# Un_TTL.net
KiCad netlist of a schematic drawn in EAGLE
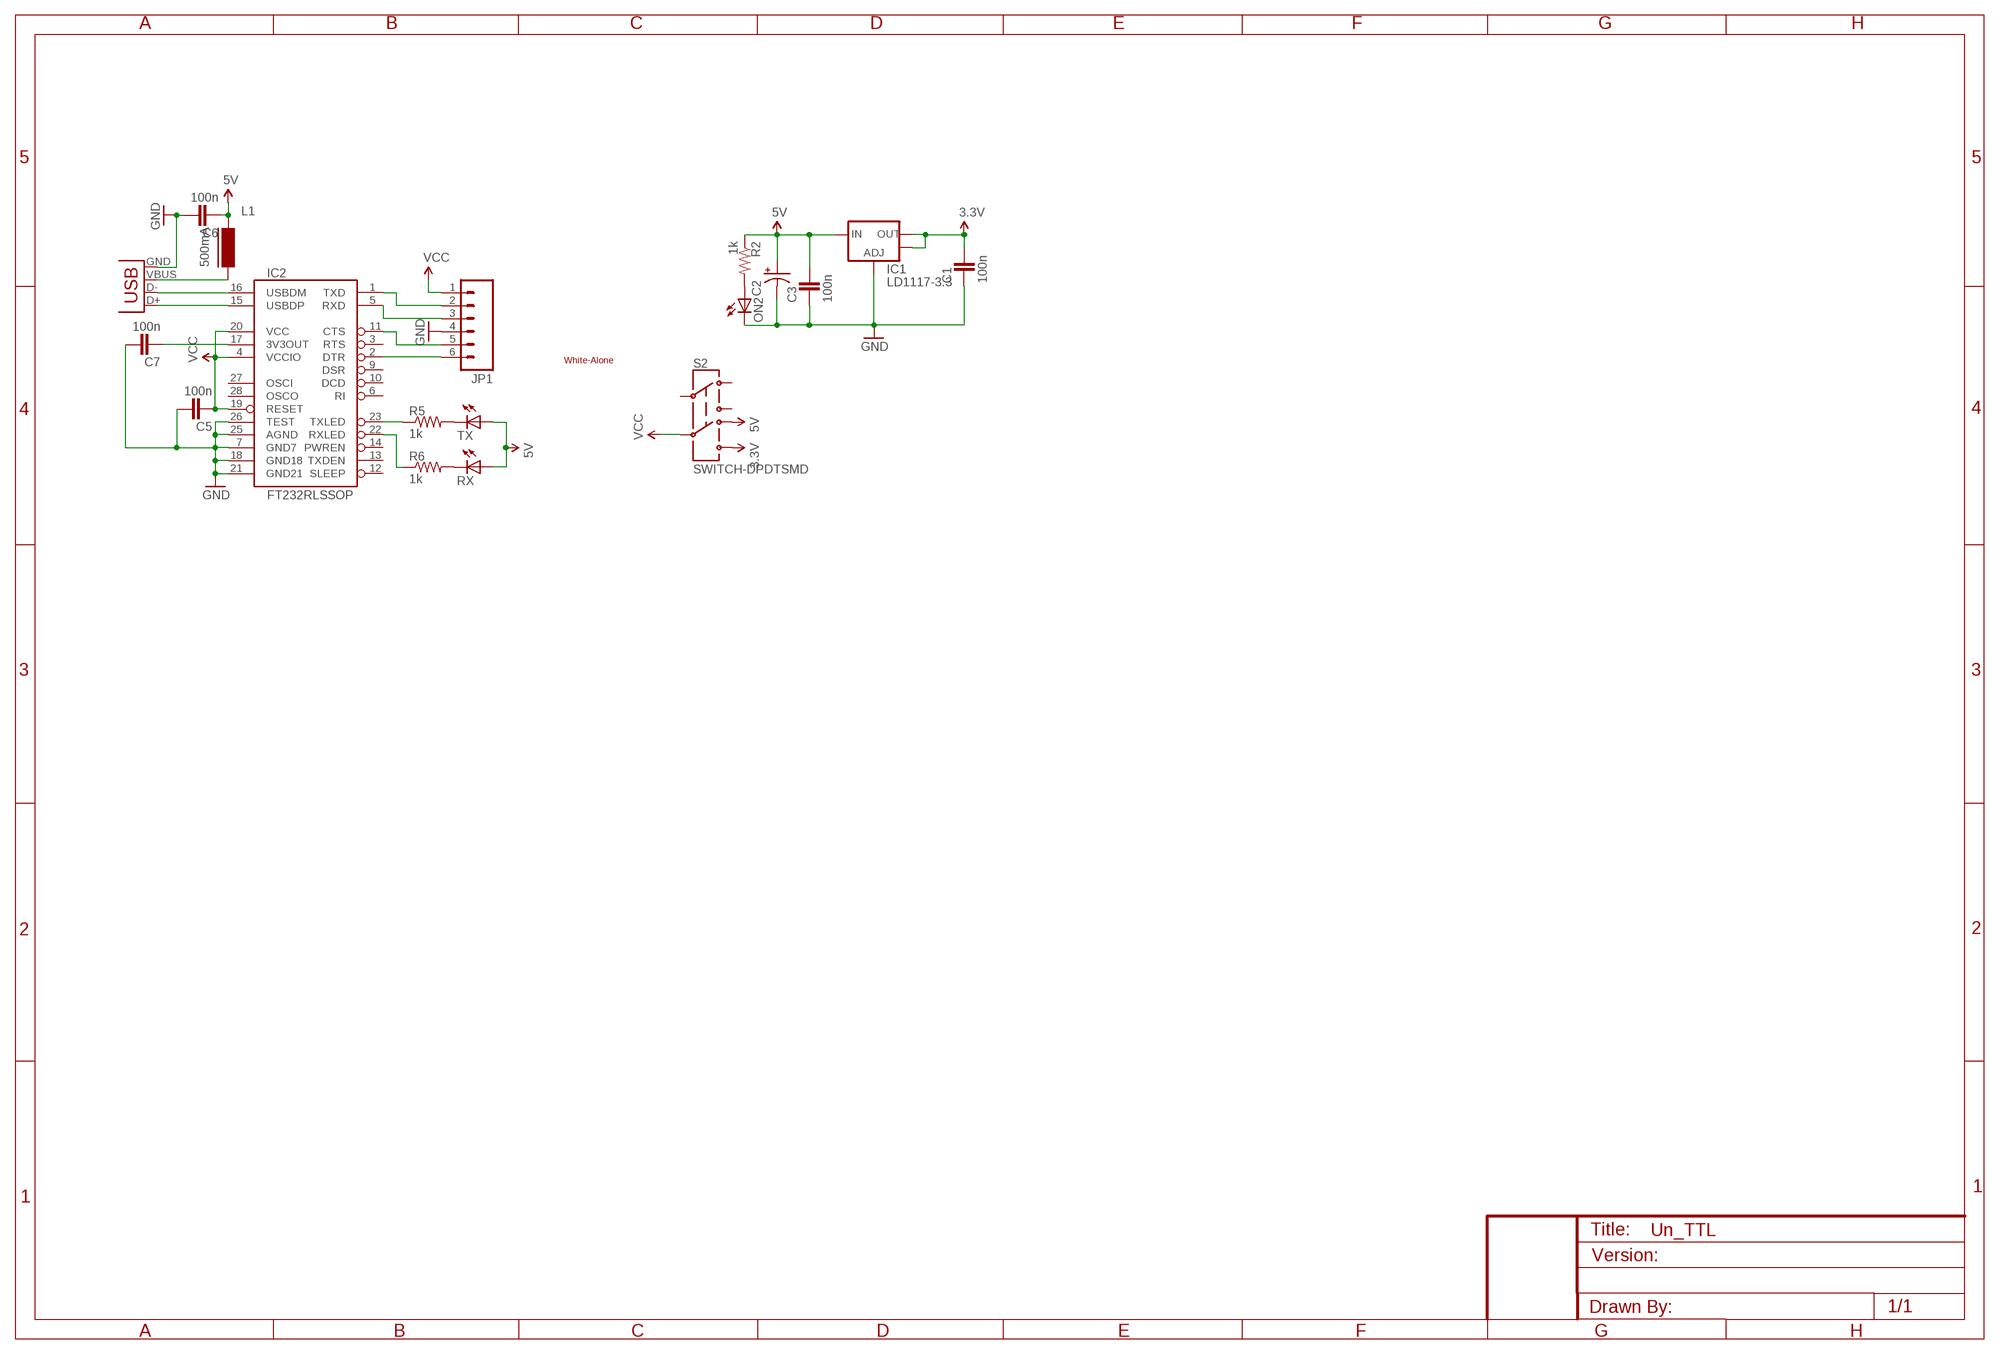
[diagram p0: schematic, sheet 1]

(export (version "E")
  (design (tool "Eeschema 10.0.6"))
  (components
    (comp (ref "C1")
      (value "100n")
      (footprint "eagle-import:0603-CAP")
      (libsource (lib "eagle-import") (part "CAP0603"))
    )
    (comp (ref "C2")
      (value "CAP_POL1206")
      (footprint "eagle-import:EIA3216")
      (libsource (lib "eagle-import") (part "CAP_POL1206"))
    )
    (comp (ref "C3")
      (value "100n")
      (footprint "eagle-import:0603-CAP")
      (libsource (lib "eagle-import") (part "CAP0603"))
    )
    (comp (ref "C5")
      (value "100n")
      (footprint "eagle-import:0603-CAP")
      (libsource (lib "eagle-import") (part "CAP0603"))
    )
    (comp (ref "C6")
      (value "100n")
      (footprint "eagle-import:0603-CAP")
      (libsource (lib "eagle-import") (part "CAP0603"))
    )
    (comp (ref "C7")
      (value "100n")
      (footprint "eagle-import:0603-CAP")
      (libsource (lib "eagle-import") (part "CAP0603"))
    )
    (comp (ref "IC1")
      (value "LD1117-3.3")
      (footprint "eagle-import:SOT223")
      (libsource (lib "eagle-import") (part "V_REG_LM1117SOT223"))
    )
    (comp (ref "IC2")
      (value "FT232RLSSOP")
      (footprint "eagle-import:SSOP28DB")
      (libsource (lib "eagle-import") (part "FT232RLSSOP"))
    )
    (comp (ref "JP1")
      (value "M06SIP")
      (footprint "eagle-import:1X06")
      (libsource (lib "eagle-import") (part "M06SIP"))
    )
    (comp (ref "L1")
      (value "500mA")
      (footprint "eagle-import:FB805")
      (libsource (lib "eagle-import") (part "FERRITE-0805"))
    )
    (comp (ref "ON2")
      (value "LED0805")
      (footprint "eagle-import:LED-0805")
      (libsource (lib "eagle-import") (part "LED0805"))
    )
    (comp (ref "R2")
      (value "1k")
      (footprint "eagle-import:0603-RES")
      (libsource (lib "eagle-import") (part "RESISTOR0603-RES"))
    )
    (comp (ref "R5")
      (value "1k")
      (footprint "eagle-import:0603-RES")
      (libsource (lib "eagle-import") (part "RESISTOR0603-RES"))
    )
    (comp (ref "R6")
      (value "1k")
      (footprint "eagle-import:0603-RES")
      (libsource (lib "eagle-import") (part "RESISTOR0603-RES"))
    )
    (comp (ref "RX")
      (value "LED0805")
      (footprint "eagle-import:LED-0805")
      (libsource (lib "eagle-import") (part "LED0805"))
    )
    (comp (ref "S2")
      (value "SWITCH-DPDTSMD")
      (footprint "eagle-import:AYZ0202")
      (libsource (lib "eagle-import") (part "SWITCH-DPDTSMD"))
    )
    (comp (ref "TX")
      (value "LED0805")
      (footprint "eagle-import:LED-0805")
      (libsource (lib "eagle-import") (part "LED0805"))
    )
    (comp (ref "U$2")
      (value "WHITE-ALONE_0")
      (footprint "eagle-import:WHITE-ALONE_0")
      (libsource (lib "eagle-import") (part "WHITE-ALONE_0"))
    )
    (comp (ref "X1")
      (value "USBSMD")
      (footprint "eagle-import:USB-MINIB")
      (libsource (lib "eagle-import") (part "USBSMD"))
    )
  )
  (nets
    (net (code "1") (name "3.3V") (class "Default")
      (node (ref "C1") (pin "1") (pinfunction "1_1") (pintype "passive"))
      (node (ref "IC1") (pin "2") (pinfunction "OUT_2") (pintype "output"))
      (node (ref "IC1") (pin "4") (pinfunction "OUT_4") (pintype "output"))
      (node (ref "S2") (pin "6") (pinfunction "6_6") (pintype "bidirectional"))
    )
    (net (code "2") (name "5V") (class "Default")
      (node (ref "C2") (pin "A") (pinfunction "+_A") (pintype "passive"))
      (node (ref "C3") (pin "1") (pinfunction "1_1") (pintype "passive"))
      (node (ref "C6") (pin "2") (pinfunction "2_2") (pintype "passive"))
      (node (ref "IC1") (pin "3") (pinfunction "IN_3") (pintype "input"))
      (node (ref "L1") (pin "1") (pinfunction "1_1") (pintype "passive"))
      (node (ref "R2") (pin "1") (pinfunction "1_1") (pintype "passive"))
      (node (ref "RX") (pin "1") (pinfunction "A_1") (pintype "passive"))
      (node (ref "S2") (pin "4") (pinfunction "4_4") (pintype "bidirectional"))
      (node (ref "TX") (pin "1") (pinfunction "A_1") (pintype "passive"))
    )
    (net (code "3") (name "GND") (class "Default")
      (node (ref "C1") (pin "2") (pinfunction "2_2") (pintype "passive"))
      (node (ref "C2") (pin "C") (pinfunction "-_C") (pintype "passive"))
      (node (ref "C3") (pin "2") (pinfunction "2_2") (pintype "passive"))
      (node (ref "C5") (pin "1") (pinfunction "1_1") (pintype "passive"))
      (node (ref "C6") (pin "1") (pinfunction "1_1") (pintype "passive"))
      (node (ref "C7") (pin "1") (pinfunction "1_1") (pintype "passive"))
      (node (ref "IC1") (pin "1") (pinfunction "ADJ_1") (pintype "input"))
      (node (ref "IC2") (pin "18") (pinfunction "GND18_18") (pintype "power_in"))
      (node (ref "IC2") (pin "21") (pinfunction "GND21_21") (pintype "power_in"))
      (node (ref "IC2") (pin "25") (pinfunction "AGND_25") (pintype "power_in"))
      (node (ref "IC2") (pin "26") (pinfunction "TEST_26") (pintype "input"))
      (node (ref "IC2") (pin "7") (pinfunction "GND7_7") (pintype "power_in"))
      (node (ref "JP1") (pin "4") (pinfunction "4_4") (pintype "passive"))
      (node (ref "ON2") (pin "2") (pinfunction "C_2") (pintype "passive"))
      (node (ref "X1") (pin "GND") (pinfunction "GND_GND") (pintype "bidirectional"))
    )
    (net (code "4") (name "Net-(IC2-3V3OUT)") (class "Default")
      (node (ref "C7") (pin "2") (pinfunction "2_2") (pintype "passive"))
      (node (ref "IC2") (pin "17") (pinfunction "3V3OUT_17") (pintype "output"))
    )
    (net (code "5") (name "Net-(IC2-CTS)") (class "Default")
      (node (ref "IC2") (pin "11") (pinfunction "CTS_11") (pintype "input"))
      (node (ref "JP1") (pin "5") (pinfunction "5_5") (pintype "passive"))
    )
    (net (code "6") (name "Net-(IC2-DTR)") (class "Default")
      (node (ref "IC2") (pin "2") (pinfunction "DTR_2") (pintype "output"))
      (node (ref "JP1") (pin "6") (pinfunction "6_6") (pintype "passive"))
    )
    (net (code "7") (name "Net-(IC2-RXD)") (class "Default")
      (node (ref "IC2") (pin "5") (pinfunction "RXD_5") (pintype "input"))
      (node (ref "JP1") (pin "3") (pinfunction "3_3") (pintype "passive"))
    )
    (net (code "8") (name "Net-(IC2-RXLED)") (class "Default")
      (node (ref "IC2") (pin "22") (pinfunction "RXLED_22") (pintype "input"))
      (node (ref "R6") (pin "1") (pinfunction "1_1") (pintype "passive"))
    )
    (net (code "9") (name "Net-(IC2-TXD)") (class "Default")
      (node (ref "IC2") (pin "1") (pinfunction "TXD_1") (pintype "output"))
      (node (ref "JP1") (pin "2") (pinfunction "2_2") (pintype "passive"))
    )
    (net (code "10") (name "Net-(IC2-TXLED)") (class "Default")
      (node (ref "IC2") (pin "23") (pinfunction "TXLED_23") (pintype "input"))
      (node (ref "R5") (pin "1") (pinfunction "1_1") (pintype "passive"))
    )
    (net (code "11") (name "Net-(IC2-USBDM)") (class "Default")
      (node (ref "IC2") (pin "16") (pinfunction "USBDM_16") (pintype "bidirectional"))
      (node (ref "X1") (pin "D-") (pinfunction "D-_D-") (pintype "bidirectional"))
    )
    (net (code "12") (name "Net-(IC2-USBDP)") (class "Default")
      (node (ref "IC2") (pin "15") (pinfunction "USBDP_15") (pintype "bidirectional"))
      (node (ref "X1") (pin "D+") (pinfunction "D+_D+") (pintype "bidirectional"))
    )
    (net (code "13") (name "Net-(L1-Pad2)") (class "Default")
      (node (ref "L1") (pin "2") (pinfunction "2_2") (pintype "passive"))
      (node (ref "X1") (pin "VBUS") (pinfunction "VBUS_VBUS") (pintype "bidirectional"))
    )
    (net (code "14") (name "Net-(ON2-A)") (class "Default")
      (node (ref "ON2") (pin "1") (pinfunction "A_1") (pintype "passive"))
      (node (ref "R2") (pin "2") (pinfunction "2_2") (pintype "passive"))
    )
    (net (code "15") (name "Net-(RX-C)") (class "Default")
      (node (ref "R6") (pin "2") (pinfunction "2_2") (pintype "passive"))
      (node (ref "RX") (pin "2") (pinfunction "C_2") (pintype "passive"))
    )
    (net (code "16") (name "Net-(TX-C)") (class "Default")
      (node (ref "R5") (pin "2") (pinfunction "2_2") (pintype "passive"))
      (node (ref "TX") (pin "2") (pinfunction "C_2") (pintype "passive"))
    )
    (net (code "17") (name "VCC") (class "Default")
      (node (ref "C5") (pin "2") (pinfunction "2_2") (pintype "passive"))
      (node (ref "IC2") (pin "19") (pinfunction "RESET_19") (pintype "input"))
      (node (ref "IC2") (pin "20") (pinfunction "VCC_20") (pintype "power_in"))
      (node (ref "IC2") (pin "4") (pinfunction "VCCIO_4") (pintype "power_in"))
      (node (ref "JP1") (pin "1") (pinfunction "1_1") (pintype "passive"))
      (node (ref "S2") (pin "5") (pinfunction "5_5") (pintype "bidirectional"))
    )
    (net (code "18") (name "unconnected-(IC2-DCD-Pad10)") (class "Default")
      (node (ref "IC2") (pin "10") (pinfunction "DCD_10") (pintype "input"))
    )
    (net (code "19") (name "unconnected-(IC2-DSR-Pad9)") (class "Default")
      (node (ref "IC2") (pin "9") (pinfunction "DSR_9") (pintype "input"))
    )
    (net (code "20") (name "unconnected-(IC2-OSCI-Pad27)") (class "Default")
      (node (ref "IC2") (pin "27") (pinfunction "OSCI_27") (pintype "input"))
    )
    (net (code "21") (name "unconnected-(IC2-OSCO-Pad28)") (class "Default")
      (node (ref "IC2") (pin "28") (pinfunction "OSCO_28") (pintype "output"))
    )
    (net (code "22") (name "unconnected-(IC2-PWREN-Pad14)") (class "Default")
      (node (ref "IC2") (pin "14") (pinfunction "PWREN_14") (pintype "input"))
    )
    (net (code "23") (name "unconnected-(IC2-RI-Pad6)") (class "Default")
      (node (ref "IC2") (pin "6") (pinfunction "RI_6") (pintype "input"))
    )
    (net (code "24") (name "unconnected-(IC2-RTS-Pad3)") (class "Default")
      (node (ref "IC2") (pin "3") (pinfunction "RTS_3") (pintype "output"))
    )
    (net (code "25") (name "unconnected-(IC2-SLEEP-Pad12)") (class "Default")
      (node (ref "IC2") (pin "12") (pinfunction "SLEEP_12") (pintype "input"))
    )
    (net (code "26") (name "unconnected-(IC2-TXDEN-Pad13)") (class "Default")
      (node (ref "IC2") (pin "13") (pinfunction "TXDEN_13") (pintype "input"))
    )
    (net (code "27") (name "unconnected-(S2-Pad1)") (class "Default")
      (node (ref "S2") (pin "1") (pinfunction "1_1") (pintype "bidirectional"))
    )
    (net (code "28") (name "unconnected-(S2-Pad2)") (class "Default")
      (node (ref "S2") (pin "2") (pinfunction "2_2") (pintype "bidirectional"))
    )
    (net (code "29") (name "unconnected-(S2-Pad3)") (class "Default")
      (node (ref "S2") (pin "3") (pinfunction "3_3") (pintype "bidirectional"))
    )
  )
)
